# 1-Schematic_NAKUJA_REMIX.net
KiCad netlist of a schematic drawn in EasyEDA
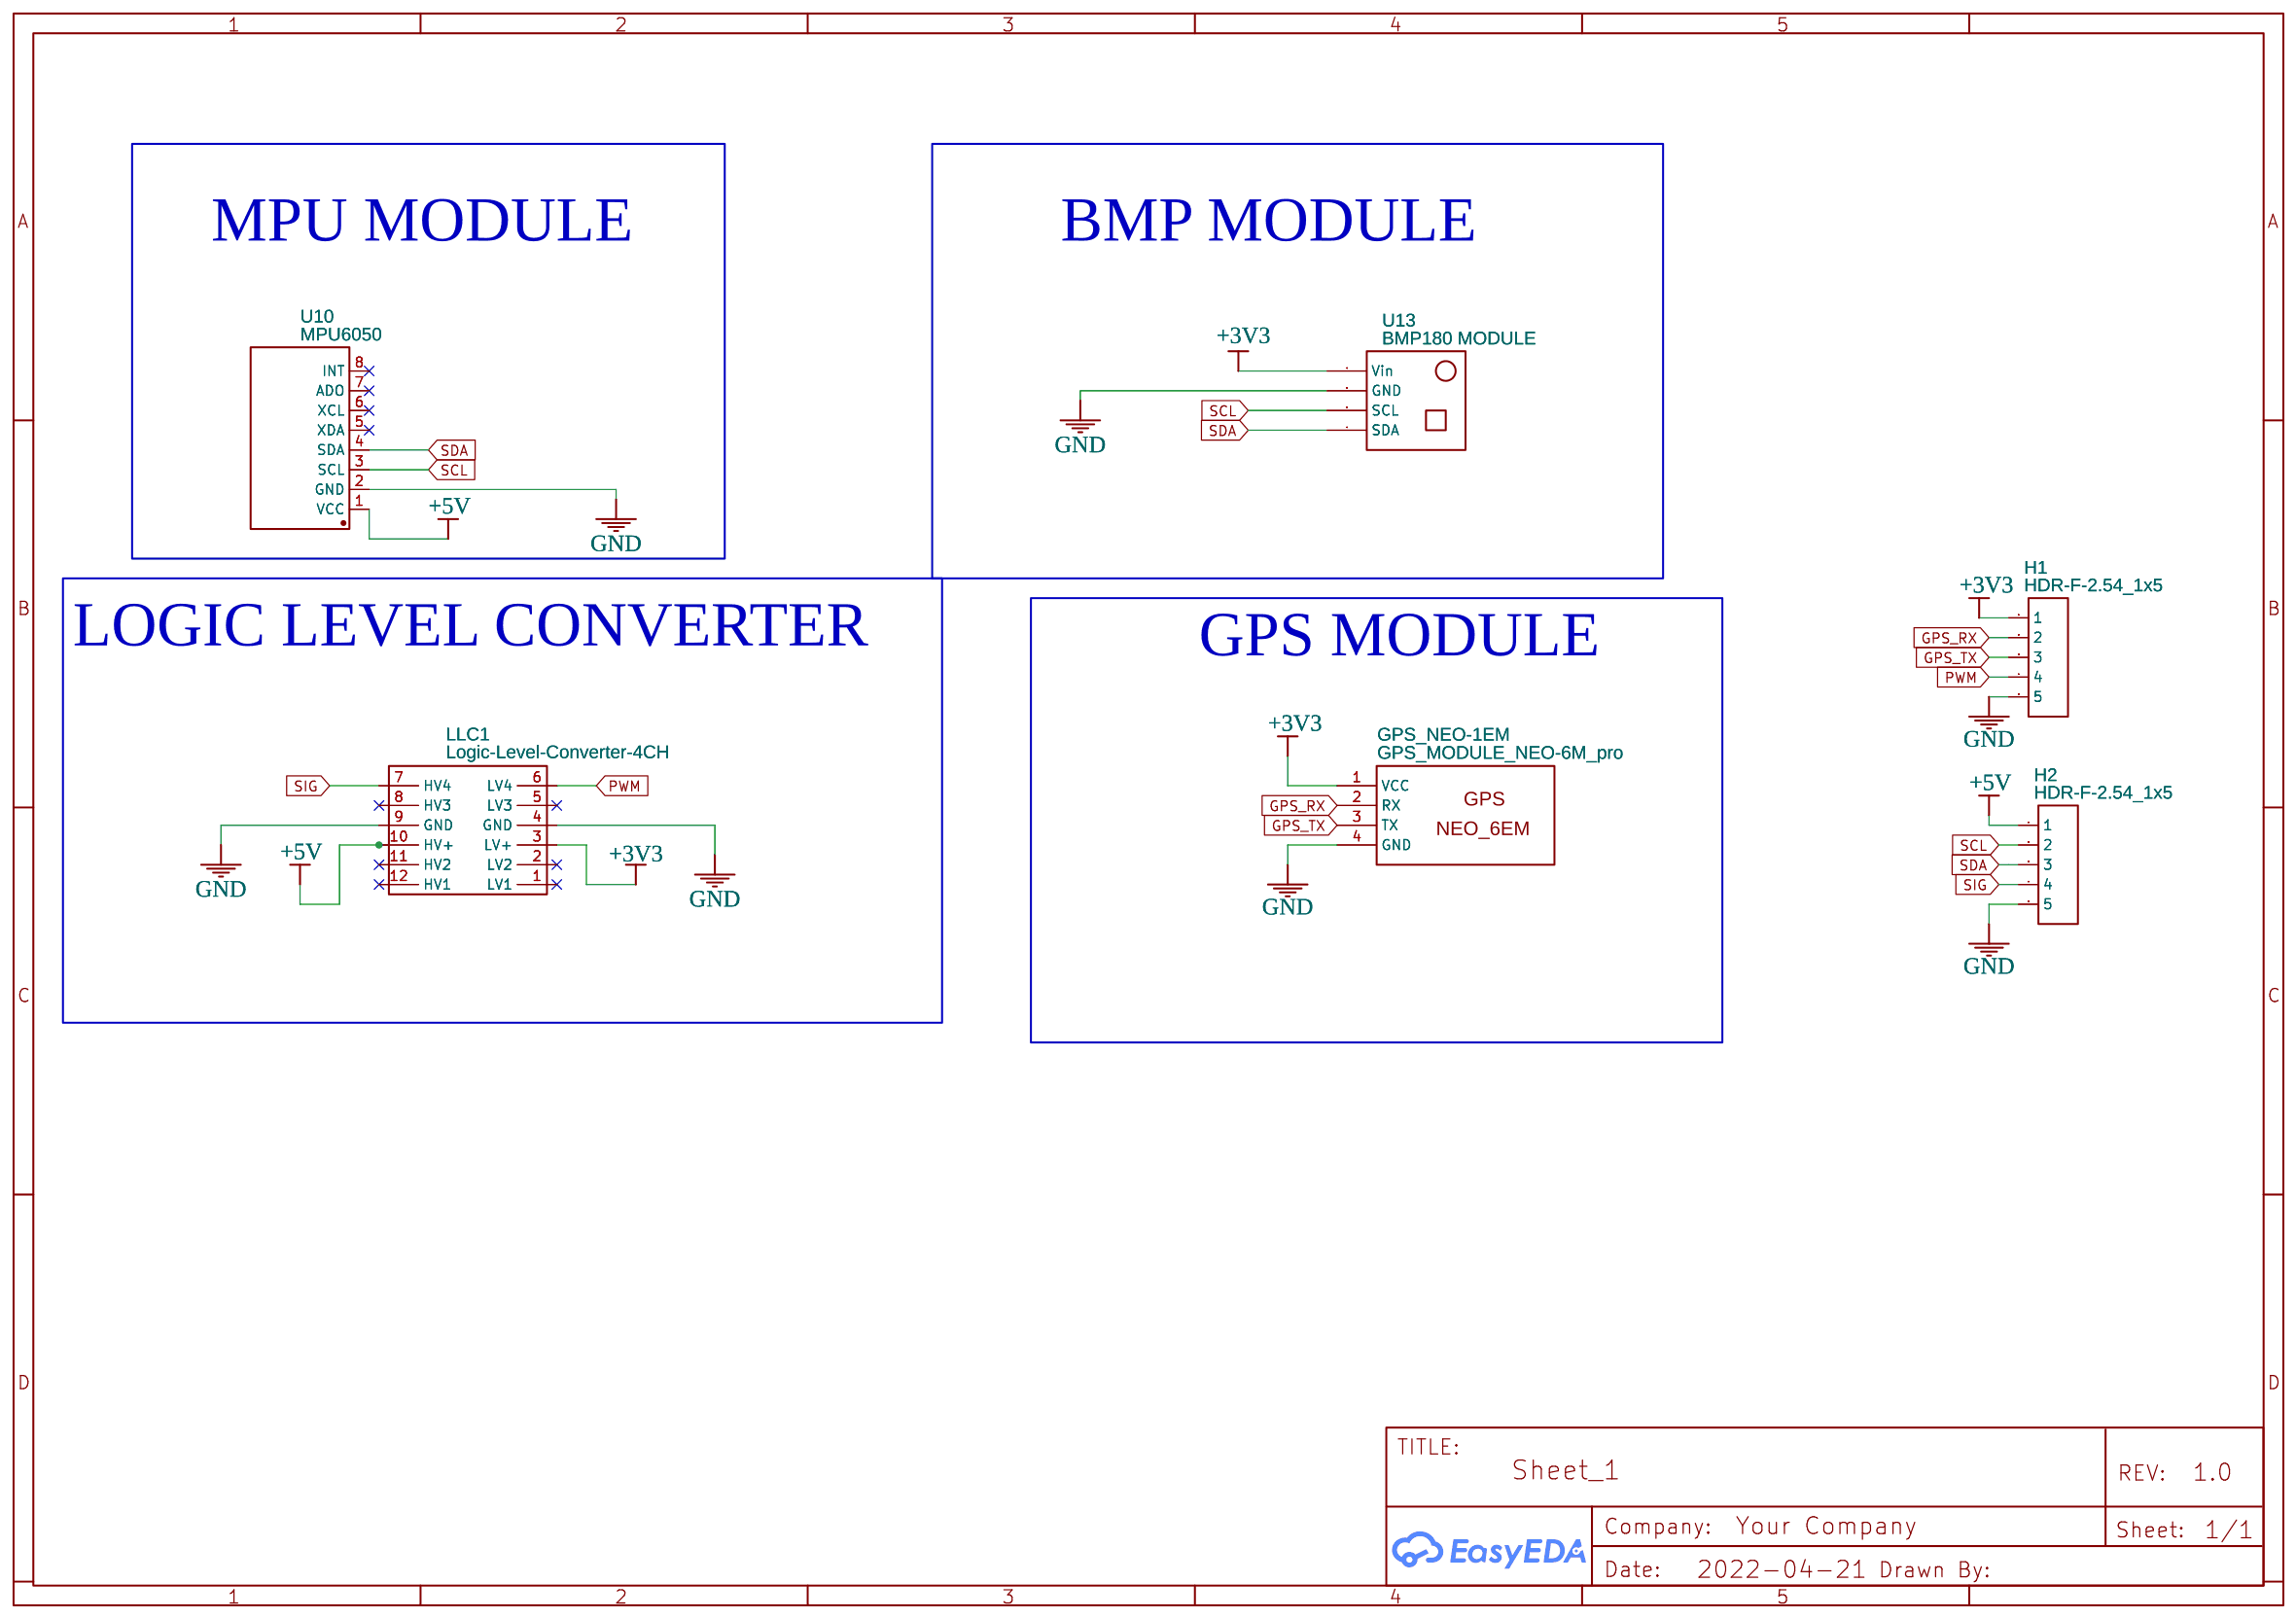
[diagram p0: schematic sheet]

(export (version "E")
  (design (tool "Eeschema 10.0.6"))
  (components
    (comp (ref "GPS_NEO-1EM")
      (value "GPS_MODULE_NEO-6M_pro")
      (libsource (lib "") (part "GPS_MODULE_NEO-6M_pro"))
    )
    (comp (ref "H1")
      (value "HDR-F-2.54_1x5")
      (fields (field (name "BOM_Supplier Part") "C50950"))
      (libsource (lib "") (part "HDR-F-2.54_1x5"))
    )
    (comp (ref "H2")
      (value "HDR-F-2.54_1x5")
      (fields (field (name "BOM_Supplier Part") "C50950"))
      (libsource (lib "") (part "HDR-F-2.54_1x5"))
    )
    (comp (ref "LLC1")
      (value "Logic-Level-Converter-4CH")
      (fields (field (name "BOM_Supplier Part") "50807"))
      (libsource (lib "") (part "Logic-Level-Converter-4CH"))
    )
    (comp (ref "U10")
      (value "MPU6050")
      (fields (field (name "BOM_Supplier Part") "GY521"))
      (libsource (lib "") (part "MPU6050"))
    )
    (comp (ref "U13")
      (value "BMP180 MODULE")
      (fields (field (name "BOM_Manufacturer Part") "BMP180 (HW-596)"))
      (libsource (lib "") (part "BMP180 MODULE"))
    )
  )
  (nets
    (net (code "1") (name "+3V3") (class "Default")
      (node (ref "GPS_NEO-1EM") (pin "1") (pinfunction "VCC_1") (pintype "passive"))
      (node (ref "H1") (pin "1") (pinfunction "1_1") (pintype "unspecified"))
      (node (ref "LLC1") (pin "3") (pinfunction "LV+_3") (pintype "unspecified"))
      (node (ref "U13") (pin "1") (pinfunction "Vin_1") (pintype "unspecified"))
    )
    (net (code "2") (name "+5V") (class "Default")
      (node (ref "H2") (pin "1") (pinfunction "1_1") (pintype "unspecified"))
      (node (ref "LLC1") (pin "10") (pinfunction "HV+_10") (pintype "unspecified"))
      (node (ref "U10") (pin "1") (pinfunction "VCC_1") (pintype "unspecified"))
    )
    (net (code "3") (name "GND") (class "Default")
      (node (ref "GPS_NEO-1EM") (pin "4") (pinfunction "GND_4") (pintype "passive"))
      (node (ref "H1") (pin "5") (pinfunction "5_5") (pintype "unspecified"))
      (node (ref "H2") (pin "5") (pinfunction "5_5") (pintype "unspecified"))
      (node (ref "LLC1") (pin "4") (pinfunction "GND_4") (pintype "unspecified"))
      (node (ref "LLC1") (pin "9") (pinfunction "GND_9") (pintype "unspecified"))
      (node (ref "U10") (pin "2") (pinfunction "GND_2") (pintype "unspecified"))
      (node (ref "U13") (pin "2") (pinfunction "GND_2") (pintype "unspecified"))
    )
    (net (code "4") (name "GPS_RX") (class "Default")
      (node (ref "GPS_NEO-1EM") (pin "2") (pinfunction "RX_2") (pintype "input"))
      (node (ref "H1") (pin "2") (pinfunction "2_2") (pintype "unspecified"))
    )
    (net (code "5") (name "GPS_TX") (class "Default")
      (node (ref "GPS_NEO-1EM") (pin "3") (pinfunction "TX_3") (pintype "output"))
      (node (ref "H1") (pin "3") (pinfunction "3_3") (pintype "unspecified"))
    )
    (net (code "6") (name "PWM") (class "Default")
      (node (ref "H1") (pin "4") (pinfunction "4_4") (pintype "unspecified"))
      (node (ref "LLC1") (pin "6") (pinfunction "LV4_6") (pintype "unspecified"))
    )
    (net (code "7") (name "SCL") (class "Default")
      (node (ref "H2") (pin "2") (pinfunction "2_2") (pintype "unspecified"))
      (node (ref "U10") (pin "3") (pinfunction "SCL_3") (pintype "unspecified"))
      (node (ref "U13") (pin "3") (pinfunction "SCL_3") (pintype "unspecified"))
    )
    (net (code "8") (name "SDA") (class "Default")
      (node (ref "H2") (pin "3") (pinfunction "3_3") (pintype "unspecified"))
      (node (ref "U10") (pin "4") (pinfunction "SDA_4") (pintype "unspecified"))
      (node (ref "U13") (pin "4") (pinfunction "SDA_4") (pintype "unspecified"))
    )
    (net (code "9") (name "SIG") (class "Default")
      (node (ref "H2") (pin "4") (pinfunction "4_4") (pintype "unspecified"))
      (node (ref "LLC1") (pin "7") (pinfunction "HV4_7") (pintype "unspecified"))
    )
    (net (code "10") (name "unconnected-(LLC1-HV1-Pad12)") (class "Default")
      (node (ref "LLC1") (pin "12") (pinfunction "HV1_12") (pintype "unspecified+no_connect"))
    )
    (net (code "11") (name "unconnected-(LLC1-HV2-Pad11)") (class "Default")
      (node (ref "LLC1") (pin "11") (pinfunction "HV2_11") (pintype "unspecified+no_connect"))
    )
    (net (code "12") (name "unconnected-(LLC1-HV3-Pad8)") (class "Default")
      (node (ref "LLC1") (pin "8") (pinfunction "HV3_8") (pintype "unspecified+no_connect"))
    )
    (net (code "13") (name "unconnected-(LLC1-LV1-Pad1)") (class "Default")
      (node (ref "LLC1") (pin "1") (pinfunction "LV1_1") (pintype "unspecified+no_connect"))
    )
    (net (code "14") (name "unconnected-(LLC1-LV2-Pad2)") (class "Default")
      (node (ref "LLC1") (pin "2") (pinfunction "LV2_2") (pintype "unspecified+no_connect"))
    )
    (net (code "15") (name "unconnected-(LLC1-LV3-Pad5)") (class "Default")
      (node (ref "LLC1") (pin "5") (pinfunction "LV3_5") (pintype "unspecified+no_connect"))
    )
    (net (code "16") (name "unconnected-(U10-ADO-Pad7)") (class "Default")
      (node (ref "U10") (pin "7") (pinfunction "ADO_7") (pintype "unspecified+no_connect"))
    )
    (net (code "17") (name "unconnected-(U10-INT-Pad8)") (class "Default")
      (node (ref "U10") (pin "8") (pinfunction "INT_8") (pintype "unspecified+no_connect"))
    )
    (net (code "18") (name "unconnected-(U10-XCL-Pad6)") (class "Default")
      (node (ref "U10") (pin "6") (pinfunction "XCL_6") (pintype "unspecified+no_connect"))
    )
    (net (code "19") (name "unconnected-(U10-XDA-Pad5)") (class "Default")
      (node (ref "U10") (pin "5") (pinfunction "XDA_5") (pintype "unspecified+no_connect"))
    )
  )
)
